# VoltageRegulator-v10-OtherMill-DoubleSid.net
KiCad netlist of a schematic drawn in EAGLE
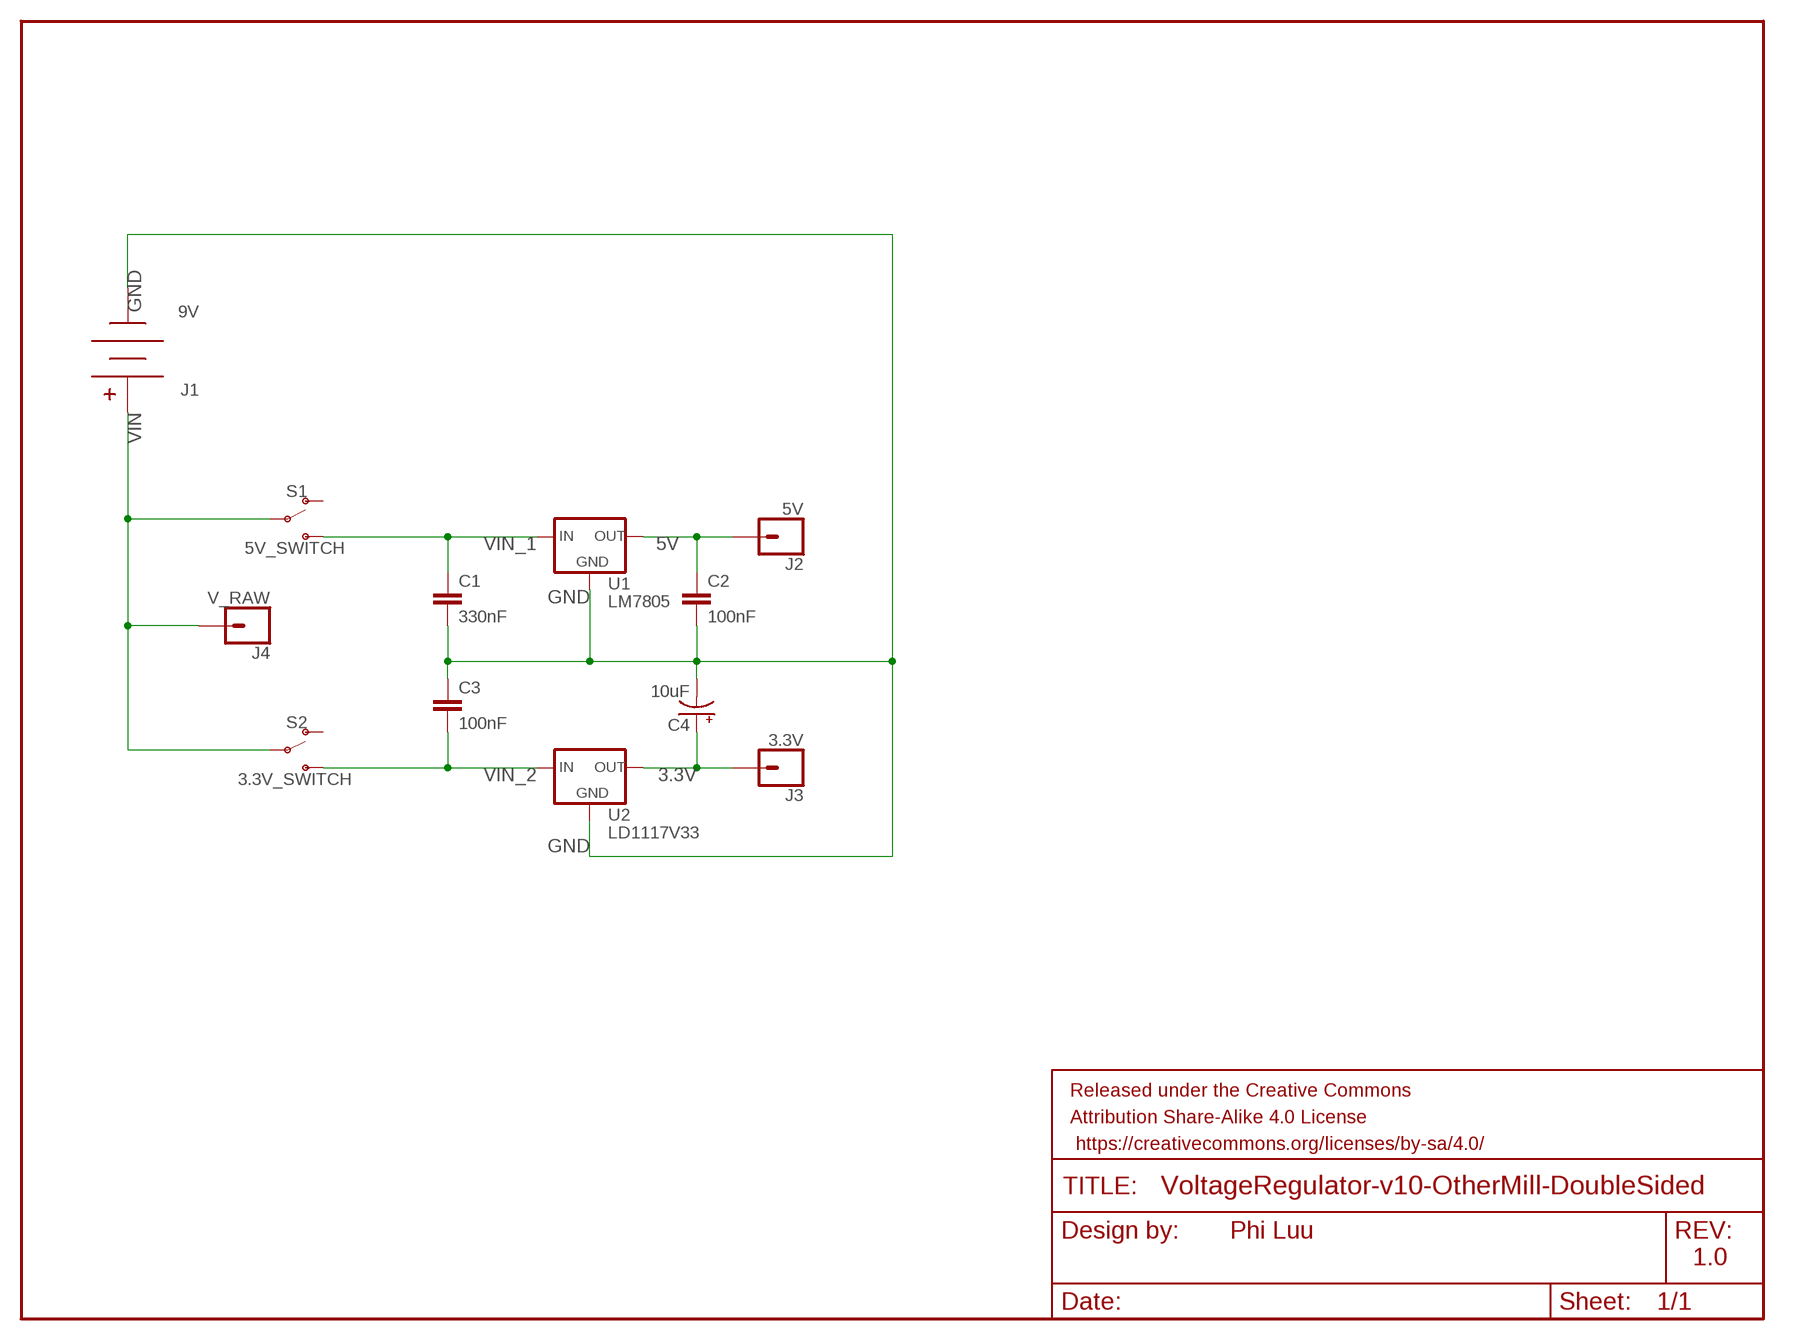
[diagram p0: schematic, sheet 1]

(export (version "E")
  (design (tool "Eeschema 10.0.6"))
  (components
    (comp (ref "C1")
      (value "330nF")
      (footprint "eagle-import:CAP-PTH-SMALL-KIT")
      (libsource (lib "eagle-import") (part "0.1UF-KIT-EZ-50V-20%"))
    )
    (comp (ref "C2")
      (value "100nF")
      (footprint "eagle-import:CAP-PTH-SMALL-KIT")
      (libsource (lib "eagle-import") (part "0.1UF-KIT-EZ-50V-20%"))
    )
    (comp (ref "C3")
      (value "100nF")
      (footprint "eagle-import:CAP-PTH-SMALL-KIT")
      (libsource (lib "eagle-import") (part "0.1UF-KIT-EZ-50V-20%"))
    )
    (comp (ref "C4")
      (value "10uF")
      (footprint "eagle-import:CPOL-RADIAL-2.5MM-5MM")
      (libsource (lib "eagle-import") (part "10UF-POLAR-RADIAL-2.5MM-25V-20%"))
    )
    (comp (ref "FRAME1")
      (value "FRAME-LETTER")
      (footprint "eagle-import:CREATIVE_COMMONS")
      (libsource (lib "eagle-import") (part "FRAME-LETTER"))
    )
    (comp (ref "J1")
      (value "9V")
      (footprint "eagle-import:BC9VPC")
      (libsource (lib "eagle-import") (part "BC9VPC"))
    )
    (comp (ref "J2")
      (value "5V")
      (footprint "eagle-import:1X01")
      (libsource (lib "eagle-import") (part "CONN_01"))
    )
    (comp (ref "J3")
      (value "3.3V")
      (footprint "eagle-import:1X01")
      (libsource (lib "eagle-import") (part "CONN_01"))
    )
    (comp (ref "J4")
      (value "V_RAW")
      (footprint "eagle-import:1X01")
      (libsource (lib "eagle-import") (part "CONN_01"))
    )
    (comp (ref "S1")
      (value "5V_SWITCH")
      (footprint "eagle-import:SWITCH_SPDT_PTH_11.6X4.0MM")
      (libsource (lib "eagle-import") (part "SWITCH-SPDT-PTH-11.6X4.0MM"))
    )
    (comp (ref "S2")
      (value "3.3V_SWITCH")
      (footprint "eagle-import:SWITCH_SPDT_PTH_11.6X4.0MM")
      (libsource (lib "eagle-import") (part "SWITCH-SPDT-PTH-11.6X4.0MM"))
    )
    (comp (ref "U1")
      (value "LM7805")
      (footprint "eagle-import:TO-220-ALT")
      (libsource (lib "eagle-import") (part "V_REG_78XX-TO-220"))
    )
    (comp (ref "U2")
      (value "LD1117V33")
      (footprint "eagle-import:78XXL")
      (libsource (lib "eagle-import") (part "V_REG_LD1117VXX"))
    )
  )
  (nets
    (net (code "1") (name "/3.3V") (class "Default")
      (node (ref "C4") (pin "1") (pinfunction "+_1") (pintype "passive"))
      (node (ref "J3") (pin "1") (pinfunction "1_1") (pintype "passive"))
      (node (ref "U2") (pin "GND") (pinfunction "OUT_GND") (pintype "passive"))
    )
    (net (code "2") (name "/5V") (class "Default")
      (node (ref "C2") (pin "1") (pinfunction "1_1") (pintype "passive"))
      (node (ref "J2") (pin "1") (pinfunction "1_1") (pintype "passive"))
      (node (ref "U1") (pin "OUT") (pinfunction "OUT_OUT") (pintype "passive"))
    )
    (net (code "3") (name "/GND") (class "Default")
      (node (ref "C1") (pin "2") (pinfunction "2_2") (pintype "passive"))
      (node (ref "C2") (pin "2") (pinfunction "2_2") (pintype "passive"))
      (node (ref "C3") (pin "1") (pinfunction "1_1") (pintype "passive"))
      (node (ref "C4") (pin "2") (pinfunction "-_2") (pintype "passive"))
      (node (ref "J1") (pin "V-") (pinfunction "V-_V-") (pintype "bidirectional"))
      (node (ref "U1") (pin "GND") (pinfunction "GND_GND") (pintype "input"))
      (node (ref "U2") (pin "IN") (pinfunction "GND_IN") (pintype "input"))
    )
    (net (code "4") (name "/VIN") (class "Default")
      (node (ref "J1") (pin "V+") (pinfunction "V+_V+") (pintype "bidirectional"))
      (node (ref "J4") (pin "1") (pinfunction "1_1") (pintype "passive"))
      (node (ref "S1") (pin "2") (pinfunction "P_2") (pintype "passive"))
      (node (ref "S2") (pin "2") (pinfunction "P_2") (pintype "passive"))
    )
    (net (code "5") (name "/VIN_1") (class "Default")
      (node (ref "C1") (pin "1") (pinfunction "1_1") (pintype "passive"))
      (node (ref "S1") (pin "3") (pinfunction "S_3") (pintype "passive"))
      (node (ref "U1") (pin "IN") (pinfunction "IN_IN") (pintype "input"))
    )
    (net (code "6") (name "/VIN_2") (class "Default")
      (node (ref "C3") (pin "2") (pinfunction "2_2") (pintype "passive"))
      (node (ref "S2") (pin "3") (pinfunction "S_3") (pintype "passive"))
      (node (ref "U2") (pin "OUT") (pinfunction "IN_OUT") (pintype "input"))
    )
    (net (code "7") (name "unconnected-(S1-O-Pad1)") (class "Default")
      (node (ref "S1") (pin "1") (pinfunction "O_1") (pintype "passive"))
    )
    (net (code "8") (name "unconnected-(S2-O-Pad1)") (class "Default")
      (node (ref "S2") (pin "1") (pinfunction "O_1") (pintype "passive"))
    )
  )
)
